# OpenOTA-SMD.net
KiCad netlist of a schematic drawn in EAGLE
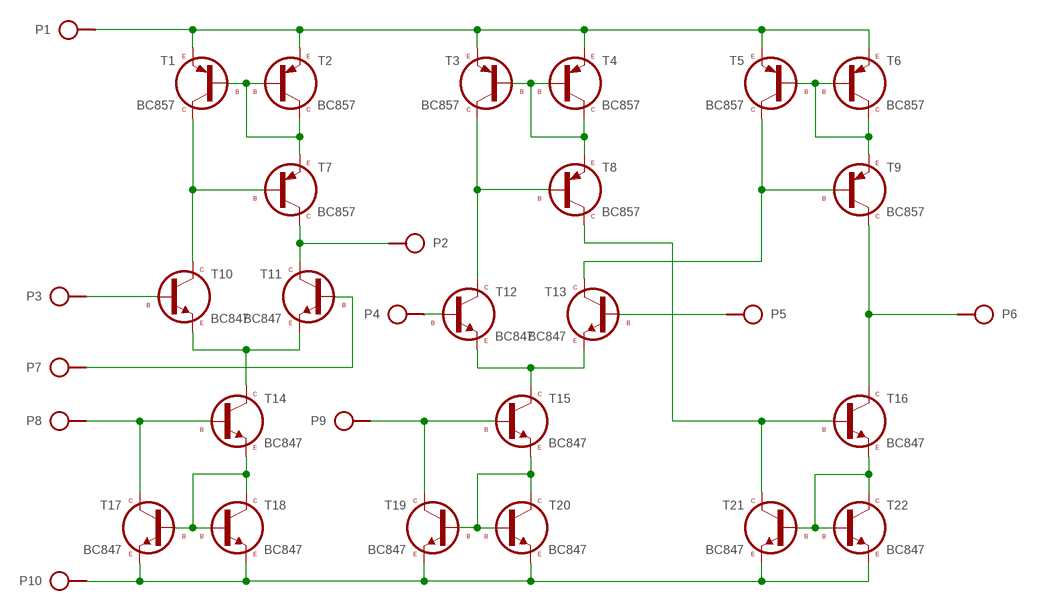
[diagram p0: schematic, sheet 1]

(export (version "E")
  (design (tool "Eeschema 10.0.6"))
  (components
    (comp (ref "P1")
      (value "SPAD")
      (footprint "eagle-import:SPAD")
      (libsource (lib "eagle-import") (part "SPAD"))
    )
    (comp (ref "P2")
      (value "SPAD")
      (footprint "eagle-import:SPAD")
      (libsource (lib "eagle-import") (part "SPAD"))
    )
    (comp (ref "P3")
      (value "SPAD")
      (footprint "eagle-import:SPAD")
      (libsource (lib "eagle-import") (part "SPAD"))
    )
    (comp (ref "P4")
      (value "SPAD")
      (footprint "eagle-import:SPAD")
      (libsource (lib "eagle-import") (part "SPAD"))
    )
    (comp (ref "P5")
      (value "SPAD")
      (footprint "eagle-import:SPAD")
      (libsource (lib "eagle-import") (part "SPAD"))
    )
    (comp (ref "P6")
      (value "SPAD")
      (footprint "eagle-import:SPAD")
      (libsource (lib "eagle-import") (part "SPAD"))
    )
    (comp (ref "P7")
      (value "SPAD")
      (footprint "eagle-import:SPAD")
      (libsource (lib "eagle-import") (part "SPAD"))
    )
    (comp (ref "P8")
      (value "SPAD")
      (footprint "eagle-import:SPAD")
      (libsource (lib "eagle-import") (part "SPAD"))
    )
    (comp (ref "P9")
      (value "SPAD")
      (footprint "eagle-import:SPAD")
      (libsource (lib "eagle-import") (part "SPAD"))
    )
    (comp (ref "P10")
      (value "SPAD")
      (footprint "eagle-import:SPAD")
      (libsource (lib "eagle-import") (part "SPAD"))
    )
    (comp (ref "T1")
      (value "BC857")
      (footprint "eagle-import:SOT-23")
      (libsource (lib "eagle-import") (part "BC857"))
    )
    (comp (ref "T2")
      (value "BC857")
      (footprint "eagle-import:SOT-23")
      (libsource (lib "eagle-import") (part "BC857"))
    )
    (comp (ref "T3")
      (value "BC857")
      (footprint "eagle-import:SOT-23")
      (libsource (lib "eagle-import") (part "BC857"))
    )
    (comp (ref "T4")
      (value "BC857")
      (footprint "eagle-import:SOT-23")
      (libsource (lib "eagle-import") (part "BC857"))
    )
    (comp (ref "T5")
      (value "BC857")
      (footprint "eagle-import:SOT-23")
      (libsource (lib "eagle-import") (part "BC857"))
    )
    (comp (ref "T6")
      (value "BC857")
      (footprint "eagle-import:SOT-23")
      (libsource (lib "eagle-import") (part "BC857"))
    )
    (comp (ref "T7")
      (value "BC857")
      (footprint "eagle-import:SOT-23")
      (libsource (lib "eagle-import") (part "BC857"))
    )
    (comp (ref "T8")
      (value "BC857")
      (footprint "eagle-import:SOT-23")
      (libsource (lib "eagle-import") (part "BC857"))
    )
    (comp (ref "T9")
      (value "BC857")
      (footprint "eagle-import:SOT-23")
      (libsource (lib "eagle-import") (part "BC857"))
    )
    (comp (ref "T10")
      (value "BC847")
      (footprint "eagle-import:SOT-23")
      (libsource (lib "eagle-import") (part "BC847"))
    )
    (comp (ref "T11")
      (value "BC847")
      (footprint "eagle-import:SOT-23")
      (libsource (lib "eagle-import") (part "BC847"))
    )
    (comp (ref "T12")
      (value "BC847")
      (footprint "eagle-import:SOT-23")
      (libsource (lib "eagle-import") (part "BC847"))
    )
    (comp (ref "T13")
      (value "BC847")
      (footprint "eagle-import:SOT-23")
      (libsource (lib "eagle-import") (part "BC847"))
    )
    (comp (ref "T14")
      (value "BC847")
      (footprint "eagle-import:SOT-23")
      (libsource (lib "eagle-import") (part "BC847"))
    )
    (comp (ref "T15")
      (value "BC847")
      (footprint "eagle-import:SOT-23")
      (libsource (lib "eagle-import") (part "BC847"))
    )
    (comp (ref "T16")
      (value "BC847")
      (footprint "eagle-import:SOT-23")
      (libsource (lib "eagle-import") (part "BC847"))
    )
    (comp (ref "T17")
      (value "BC847")
      (footprint "eagle-import:SOT-23")
      (libsource (lib "eagle-import") (part "BC847"))
    )
    (comp (ref "T18")
      (value "BC847")
      (footprint "eagle-import:SOT-23")
      (libsource (lib "eagle-import") (part "BC847"))
    )
    (comp (ref "T19")
      (value "BC847")
      (footprint "eagle-import:SOT-23")
      (libsource (lib "eagle-import") (part "BC847"))
    )
    (comp (ref "T20")
      (value "BC847")
      (footprint "eagle-import:SOT-23")
      (libsource (lib "eagle-import") (part "BC847"))
    )
    (comp (ref "T21")
      (value "BC847")
      (footprint "eagle-import:SOT-23")
      (libsource (lib "eagle-import") (part "BC847"))
    )
    (comp (ref "T22")
      (value "BC847")
      (footprint "eagle-import:SOT-23")
      (libsource (lib "eagle-import") (part "BC847"))
    )
  )
  (nets
    (net (code "1") (name "Net-(P1-P$1)") (class "Default")
      (node (ref "P1") (pin "1") (pinfunction "P$1_1") (pintype "passive"))
      (node (ref "T1") (pin "2") (pinfunction "E_2") (pintype "passive"))
      (node (ref "T2") (pin "2") (pinfunction "E_2") (pintype "passive"))
      (node (ref "T3") (pin "2") (pinfunction "E_2") (pintype "passive"))
      (node (ref "T4") (pin "2") (pinfunction "E_2") (pintype "passive"))
      (node (ref "T5") (pin "2") (pinfunction "E_2") (pintype "passive"))
      (node (ref "T6") (pin "2") (pinfunction "E_2") (pintype "passive"))
    )
    (net (code "2") (name "Net-(P2-P$1)") (class "Default")
      (node (ref "P2") (pin "1") (pinfunction "P$1_1") (pintype "passive"))
      (node (ref "T11") (pin "3") (pinfunction "C_3") (pintype "passive"))
      (node (ref "T7") (pin "3") (pinfunction "C_3") (pintype "passive"))
    )
    (net (code "3") (name "Net-(P3-P$1)") (class "Default")
      (node (ref "P3") (pin "1") (pinfunction "P$1_1") (pintype "passive"))
      (node (ref "T10") (pin "1") (pinfunction "B_1") (pintype "passive"))
    )
    (net (code "4") (name "Net-(P4-P$1)") (class "Default")
      (node (ref "P4") (pin "1") (pinfunction "P$1_1") (pintype "passive"))
      (node (ref "T12") (pin "1") (pinfunction "B_1") (pintype "passive"))
    )
    (net (code "5") (name "Net-(P5-P$1)") (class "Default")
      (node (ref "P5") (pin "1") (pinfunction "P$1_1") (pintype "passive"))
      (node (ref "T13") (pin "1") (pinfunction "B_1") (pintype "passive"))
    )
    (net (code "6") (name "Net-(P6-P$1)") (class "Default")
      (node (ref "P6") (pin "1") (pinfunction "P$1_1") (pintype "passive"))
      (node (ref "T16") (pin "3") (pinfunction "C_3") (pintype "passive"))
      (node (ref "T9") (pin "3") (pinfunction "C_3") (pintype "passive"))
    )
    (net (code "7") (name "Net-(P7-P$1)") (class "Default")
      (node (ref "P7") (pin "1") (pinfunction "P$1_1") (pintype "passive"))
      (node (ref "T11") (pin "1") (pinfunction "B_1") (pintype "passive"))
    )
    (net (code "8") (name "Net-(P8-P$1)") (class "Default")
      (node (ref "P8") (pin "1") (pinfunction "P$1_1") (pintype "passive"))
      (node (ref "T14") (pin "1") (pinfunction "B_1") (pintype "passive"))
      (node (ref "T17") (pin "3") (pinfunction "C_3") (pintype "passive"))
    )
    (net (code "9") (name "Net-(P9-P$1)") (class "Default")
      (node (ref "P9") (pin "1") (pinfunction "P$1_1") (pintype "passive"))
      (node (ref "T15") (pin "1") (pinfunction "B_1") (pintype "passive"))
      (node (ref "T19") (pin "3") (pinfunction "C_3") (pintype "passive"))
    )
    (net (code "10") (name "Net-(P10-P$1)") (class "Default")
      (node (ref "P10") (pin "1") (pinfunction "P$1_1") (pintype "passive"))
      (node (ref "T17") (pin "2") (pinfunction "E_2") (pintype "passive"))
      (node (ref "T18") (pin "2") (pinfunction "E_2") (pintype "passive"))
      (node (ref "T19") (pin "2") (pinfunction "E_2") (pintype "passive"))
      (node (ref "T20") (pin "2") (pinfunction "E_2") (pintype "passive"))
      (node (ref "T21") (pin "2") (pinfunction "E_2") (pintype "passive"))
      (node (ref "T22") (pin "2") (pinfunction "E_2") (pintype "passive"))
    )
    (net (code "11") (name "Net-(T1-B)") (class "Default")
      (node (ref "T1") (pin "1") (pinfunction "B_1") (pintype "passive"))
      (node (ref "T2") (pin "1") (pinfunction "B_1") (pintype "passive"))
      (node (ref "T2") (pin "3") (pinfunction "C_3") (pintype "passive"))
      (node (ref "T7") (pin "2") (pinfunction "E_2") (pintype "passive"))
    )
    (net (code "12") (name "Net-(T1-C)") (class "Default")
      (node (ref "T1") (pin "3") (pinfunction "C_3") (pintype "passive"))
      (node (ref "T10") (pin "3") (pinfunction "C_3") (pintype "passive"))
      (node (ref "T7") (pin "1") (pinfunction "B_1") (pintype "passive"))
    )
    (net (code "13") (name "Net-(T3-B)") (class "Default")
      (node (ref "T3") (pin "1") (pinfunction "B_1") (pintype "passive"))
      (node (ref "T4") (pin "1") (pinfunction "B_1") (pintype "passive"))
      (node (ref "T4") (pin "3") (pinfunction "C_3") (pintype "passive"))
      (node (ref "T8") (pin "2") (pinfunction "E_2") (pintype "passive"))
    )
    (net (code "14") (name "Net-(T5-B)") (class "Default")
      (node (ref "T5") (pin "1") (pinfunction "B_1") (pintype "passive"))
      (node (ref "T6") (pin "1") (pinfunction "B_1") (pintype "passive"))
      (node (ref "T6") (pin "3") (pinfunction "C_3") (pintype "passive"))
      (node (ref "T9") (pin "2") (pinfunction "E_2") (pintype "passive"))
    )
    (net (code "15") (name "Net-(T10-E)") (class "Default")
      (node (ref "T10") (pin "2") (pinfunction "E_2") (pintype "passive"))
      (node (ref "T11") (pin "2") (pinfunction "E_2") (pintype "passive"))
      (node (ref "T14") (pin "3") (pinfunction "C_3") (pintype "passive"))
    )
    (net (code "16") (name "Net-(T12-C)") (class "Default")
      (node (ref "T12") (pin "3") (pinfunction "C_3") (pintype "passive"))
      (node (ref "T3") (pin "3") (pinfunction "C_3") (pintype "passive"))
      (node (ref "T8") (pin "1") (pinfunction "B_1") (pintype "passive"))
    )
    (net (code "17") (name "Net-(T12-E)") (class "Default")
      (node (ref "T12") (pin "2") (pinfunction "E_2") (pintype "passive"))
      (node (ref "T13") (pin "2") (pinfunction "E_2") (pintype "passive"))
      (node (ref "T15") (pin "3") (pinfunction "C_3") (pintype "passive"))
    )
    (net (code "18") (name "Net-(T13-C)") (class "Default")
      (node (ref "T13") (pin "3") (pinfunction "C_3") (pintype "passive"))
      (node (ref "T5") (pin "3") (pinfunction "C_3") (pintype "passive"))
      (node (ref "T9") (pin "1") (pinfunction "B_1") (pintype "passive"))
    )
    (net (code "19") (name "Net-(T14-E)") (class "Default")
      (node (ref "T14") (pin "2") (pinfunction "E_2") (pintype "passive"))
      (node (ref "T17") (pin "1") (pinfunction "B_1") (pintype "passive"))
      (node (ref "T18") (pin "1") (pinfunction "B_1") (pintype "passive"))
      (node (ref "T18") (pin "3") (pinfunction "C_3") (pintype "passive"))
    )
    (net (code "20") (name "Net-(T15-E)") (class "Default")
      (node (ref "T15") (pin "2") (pinfunction "E_2") (pintype "passive"))
      (node (ref "T19") (pin "1") (pinfunction "B_1") (pintype "passive"))
      (node (ref "T20") (pin "1") (pinfunction "B_1") (pintype "passive"))
      (node (ref "T20") (pin "3") (pinfunction "C_3") (pintype "passive"))
    )
    (net (code "21") (name "Net-(T16-B)") (class "Default")
      (node (ref "T16") (pin "1") (pinfunction "B_1") (pintype "passive"))
      (node (ref "T21") (pin "3") (pinfunction "C_3") (pintype "passive"))
      (node (ref "T8") (pin "3") (pinfunction "C_3") (pintype "passive"))
    )
    (net (code "22") (name "Net-(T16-E)") (class "Default")
      (node (ref "T16") (pin "2") (pinfunction "E_2") (pintype "passive"))
      (node (ref "T21") (pin "1") (pinfunction "B_1") (pintype "passive"))
      (node (ref "T22") (pin "1") (pinfunction "B_1") (pintype "passive"))
      (node (ref "T22") (pin "3") (pinfunction "C_3") (pintype "passive"))
    )
  )
)
